# Sheet1.net
KiCad netlist of a schematic drawn in Altium Designer
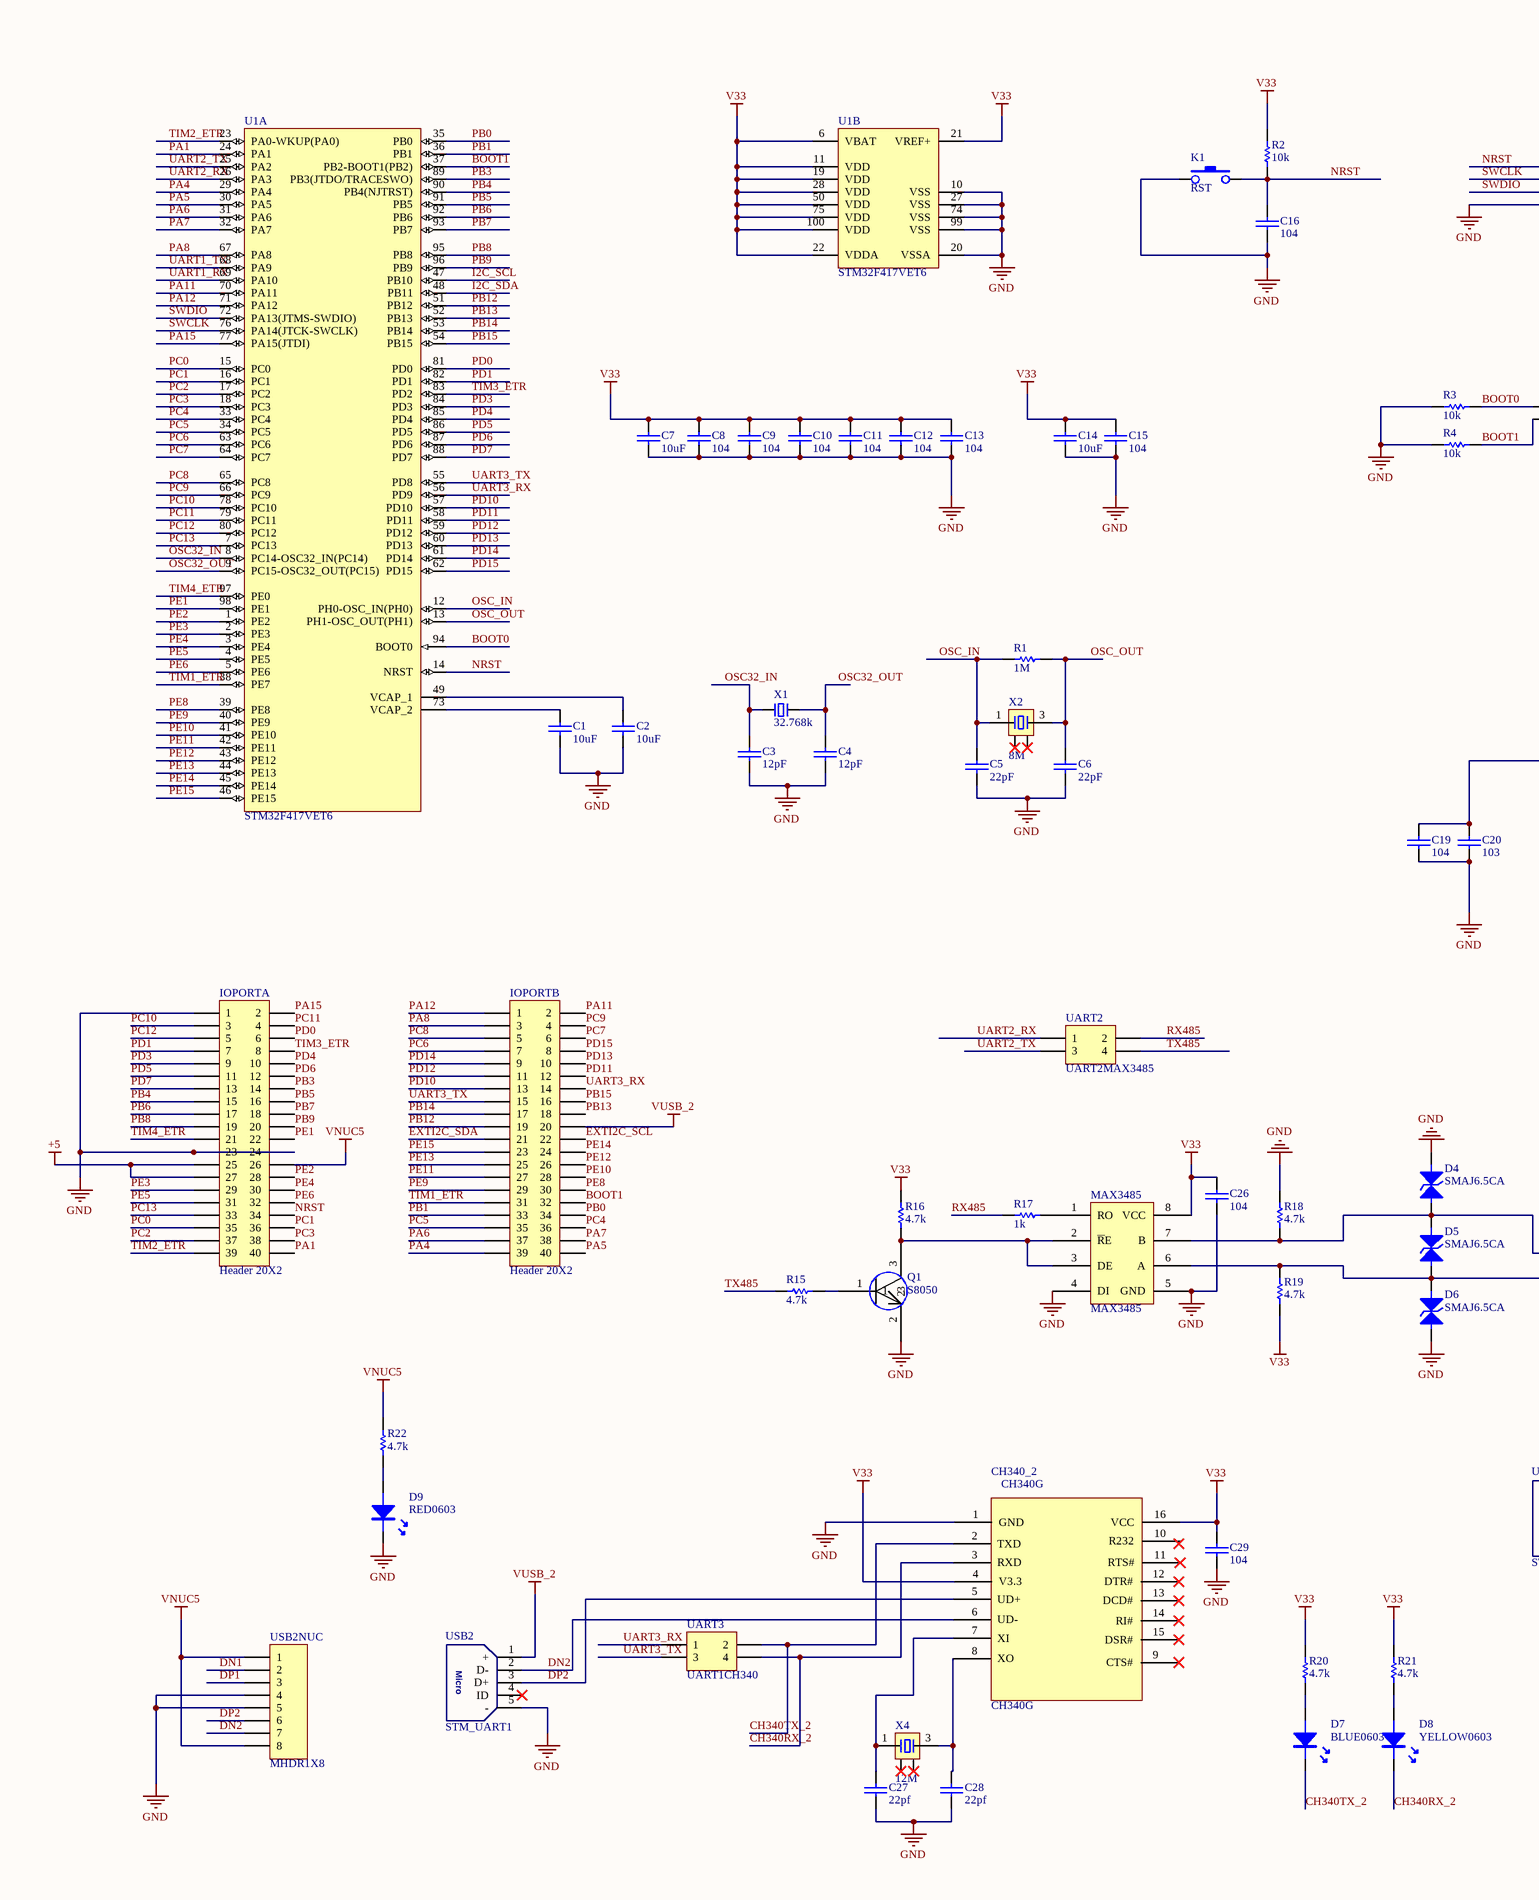
[diagram p0: Sheet1.SchDoc, left]
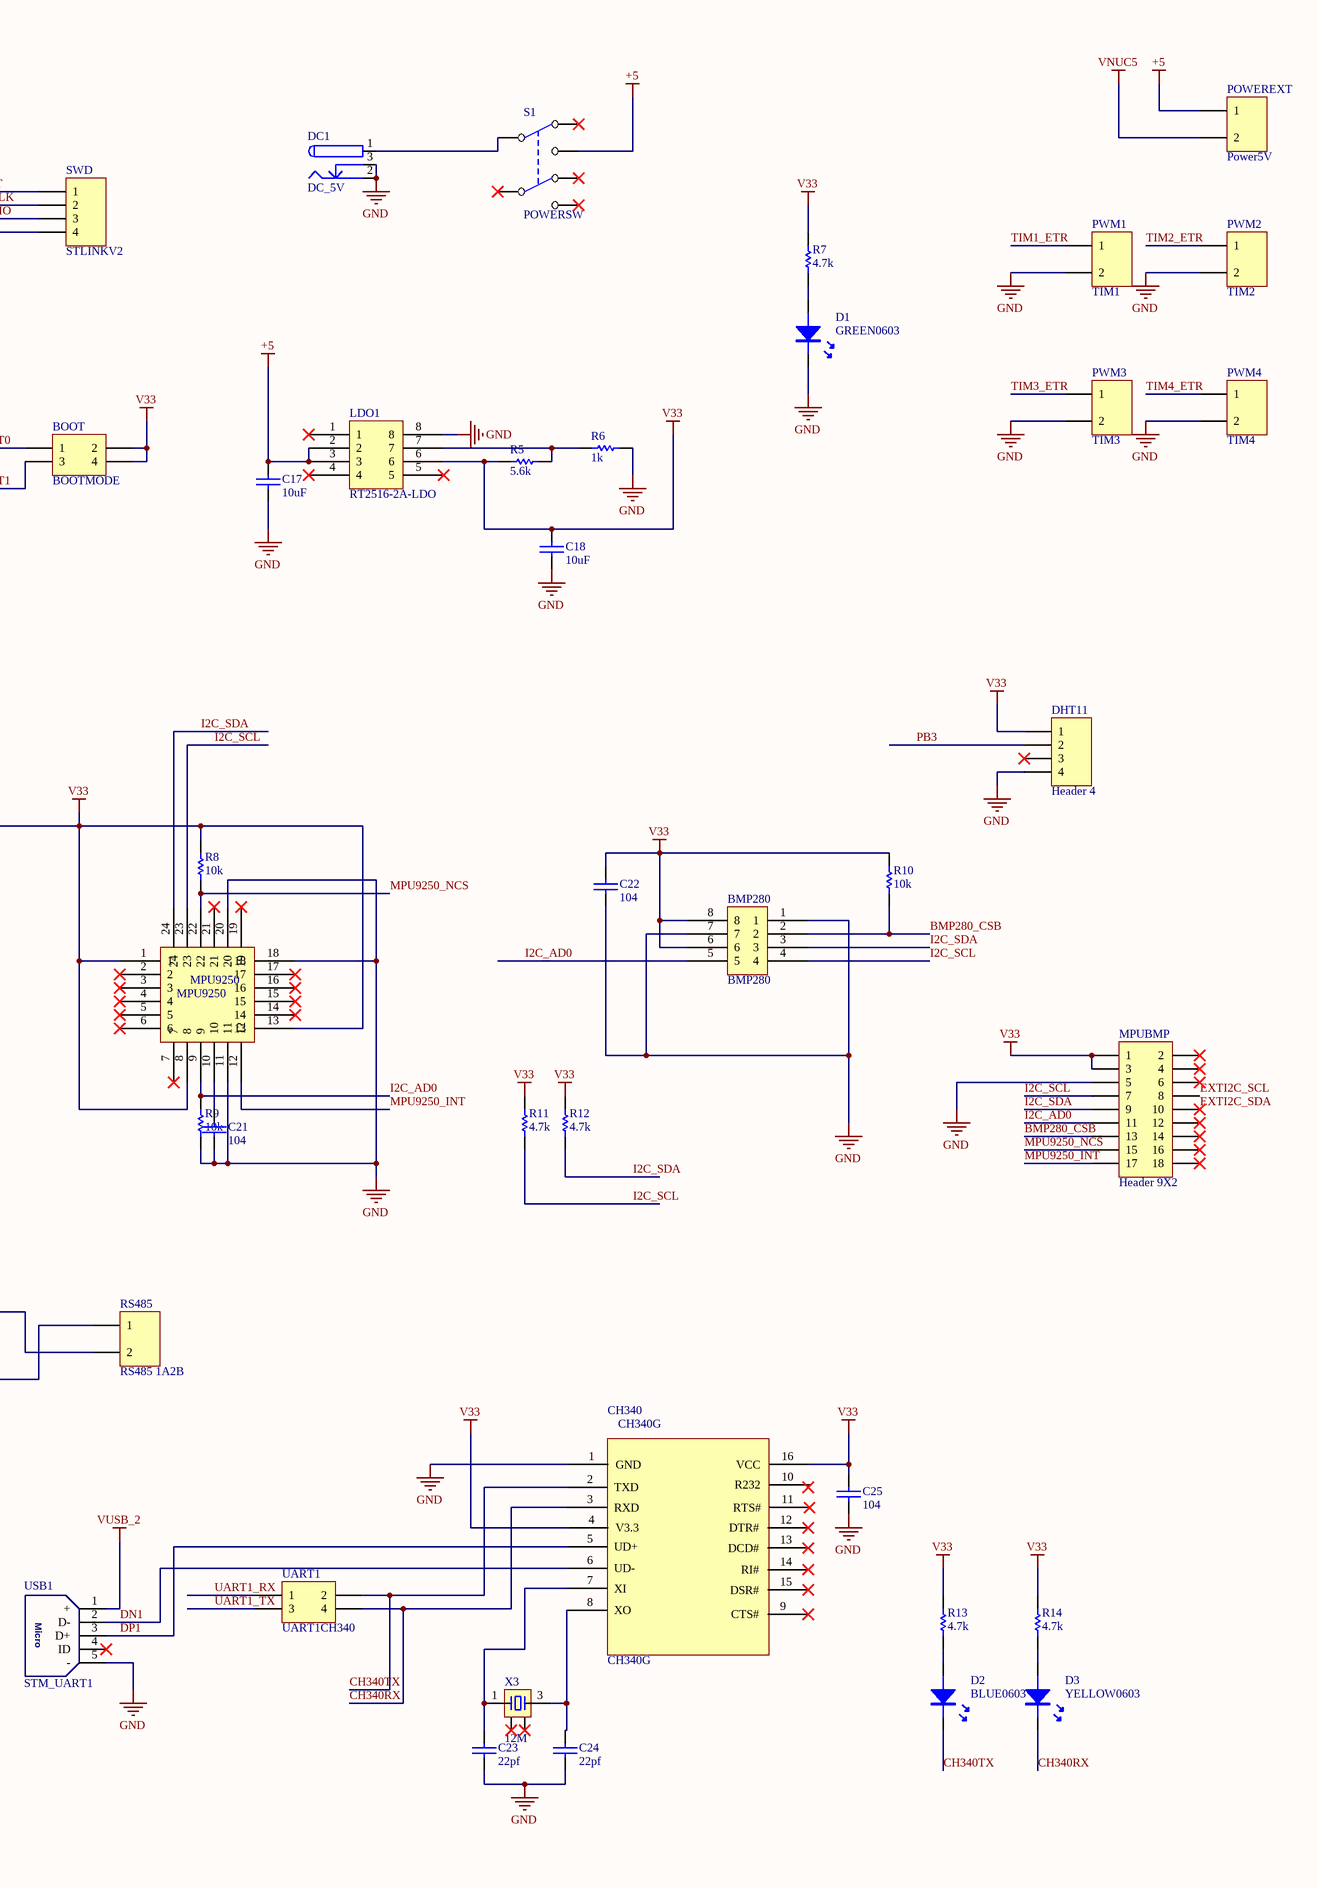
[diagram p1: Sheet1.SchDoc, right]

(export (version "E")
  (design (tool "Eeschema 10.0.6"))
  (components
    (comp (ref "BMP280")
      (value "BMP280")
      (footprint "LGA8-BOSCH")
      (libsource (lib "ics") (part "LGA8-BOSCH"))
    )
    (comp (ref "BOOT")
      (value "BOOTMODE")
      (footprint "HDR2X2")
      (description "Header, 2-Pin, Dual row")
      (fields (field (name "PUBLISHER") "Altium Limited"))
      (libsource (lib "Miscellaneous Connectors") (part "Header 2X2"))
    )
    (comp (ref "C1")
      (value "10uF")
      (footprint "0805C")
      (description "无极性电容")
      (libsource (lib "Capacitance") (part "CAP"))
    )
    (comp (ref "C2")
      (value "10uF")
      (footprint "0805C")
      (description "无极性电容")
      (libsource (lib "Capacitance") (part "CAP"))
    )
    (comp (ref "C3")
      (value "12pF")
      (footprint "0603C")
      (description "无极性电容")
      (libsource (lib "Capacitance") (part "CAP"))
    )
    (comp (ref "C4")
      (value "12pF")
      (footprint "0603C")
      (description "无极性电容")
      (libsource (lib "Capacitance") (part "CAP"))
    )
    (comp (ref "C5")
      (value "22pF")
      (footprint "0603C")
      (description "无极性电容")
      (libsource (lib "Capacitance") (part "CAP"))
    )
    (comp (ref "C6")
      (value "22pF")
      (footprint "0603C")
      (description "无极性电容")
      (libsource (lib "Capacitance") (part "CAP"))
    )
    (comp (ref "C7")
      (value "10uF")
      (footprint "0805C")
      (description "无极性电容")
      (libsource (lib "Capacitance") (part "CAP"))
    )
    (comp (ref "C8")
      (value "104")
      (footprint "0603C")
      (description "无极性电容")
      (libsource (lib "Capacitance") (part "CAP"))
    )
    (comp (ref "C9")
      (value "104")
      (footprint "0603C")
      (description "无极性电容")
      (libsource (lib "Capacitance") (part "CAP"))
    )
    (comp (ref "C10")
      (value "104")
      (footprint "0603C")
      (description "无极性电容")
      (libsource (lib "Capacitance") (part "CAP"))
    )
    (comp (ref "C11")
      (value "104")
      (footprint "0603C")
      (description "无极性电容")
      (libsource (lib "Capacitance") (part "CAP"))
    )
    (comp (ref "C12")
      (value "104")
      (footprint "0603C")
      (description "无极性电容")
      (libsource (lib "Capacitance") (part "CAP"))
    )
    (comp (ref "C13")
      (value "104")
      (footprint "0603C")
      (description "无极性电容")
      (libsource (lib "Capacitance") (part "CAP"))
    )
    (comp (ref "C14")
      (value "10uF")
      (footprint "0805C")
      (description "无极性电容")
      (libsource (lib "Capacitance") (part "CAP"))
    )
    (comp (ref "C15")
      (value "104")
      (footprint "0603C")
      (description "无极性电容")
      (libsource (lib "Capacitance") (part "CAP"))
    )
    (comp (ref "C16")
      (value "104")
      (footprint "0603C")
      (description "无极性电容")
      (libsource (lib "Capacitance") (part "CAP"))
    )
    (comp (ref "C17")
      (value "10uF")
      (footprint "0805C")
      (description "无极性电容")
      (libsource (lib "Capacitance") (part "CAP"))
    )
    (comp (ref "C18")
      (value "10uF")
      (footprint "0805C")
      (description "无极性电容")
      (libsource (lib "Capacitance") (part "CAP"))
    )
    (comp (ref "C19")
      (value "104")
      (footprint "0603C")
      (description "无极性电容")
      (libsource (lib "Capacitance") (part "CAP"))
    )
    (comp (ref "C20")
      (value "103")
      (footprint "0603C")
      (description "无极性电容")
      (libsource (lib "Capacitance") (part "CAP"))
    )
    (comp (ref "C21")
      (value "104")
      (footprint "0603C")
      (description "无极性电容")
      (libsource (lib "Capacitance") (part "CAP"))
    )
    (comp (ref "C22")
      (value "104")
      (footprint "0603C")
      (description "无极性电容")
      (libsource (lib "Capacitance") (part "CAP"))
    )
    (comp (ref "C23")
      (value "22pf")
      (footprint "0603C")
      (description "无极性电容")
      (libsource (lib "Capacitance") (part "CAP"))
    )
    (comp (ref "C24")
      (value "22pf")
      (footprint "0603C")
      (description "无极性电容")
      (libsource (lib "Capacitance") (part "CAP"))
    )
    (comp (ref "C25")
      (value "104")
      (footprint "0603C")
      (description "无极性电容")
      (libsource (lib "Capacitance") (part "CAP"))
    )
    (comp (ref "C26")
      (value "104")
      (footprint "0805C")
      (description "无极性电容")
      (libsource (lib "Capacitance") (part "CAP"))
    )
    (comp (ref "C27")
      (value "22pf")
      (footprint "0603C")
      (description "无极性电容")
      (libsource (lib "Capacitance") (part "CAP"))
    )
    (comp (ref "C28")
      (value "22pf")
      (footprint "0603C")
      (description "无极性电容")
      (libsource (lib "Capacitance") (part "CAP"))
    )
    (comp (ref "C29")
      (value "104")
      (footprint "0603C")
      (description "无极性电容")
      (libsource (lib "Capacitance") (part "CAP"))
    )
    (comp (ref "CH340")
      (value "CH340G")
      (footprint "SOIC127P600X170-16N")
      (libsource (lib "CH340G") (part "Component_1"))
    )
    (comp (ref "CH340_2")
      (value "CH340G")
      (footprint "SOIC127P600X170-16N")
      (libsource (lib "CH340G") (part "Component_1"))
    )
    (comp (ref "D1") (value "GREEN0603") (footprint "LED-0603G") (libsource (lib "LED") (part "LED")))
    (comp (ref "D2") (value "BLUE0603") (footprint "LED-0603B") (libsource (lib "LED") (part "LED")))
    (comp (ref "D3") (value "YELLOW0603") (footprint "LED-0603Y") (libsource (lib "LED") (part "LED")))
    (comp (ref "D4")
      (value "SMAJ6.5CA")
      (footprint "SMA/DO-214AC")
      (description "双向瞬态抑制二极管")
      (libsource (lib "DIODE") (part "TVS"))
    )
    (comp (ref "D5")
      (value "SMAJ6.5CA")
      (footprint "SMA/DO-214AC")
      (description "双向瞬态抑制二极管")
      (libsource (lib "DIODE") (part "TVS"))
    )
    (comp (ref "D6")
      (value "SMAJ6.5CA")
      (footprint "SMA/DO-214AC")
      (description "双向瞬态抑制二极管")
      (libsource (lib "DIODE") (part "TVS"))
    )
    (comp (ref "D7") (value "BLUE0603") (footprint "LED-0603B") (libsource (lib "LED") (part "LED")))
    (comp (ref "D8") (value "YELLOW0603") (footprint "LED-0603Y") (libsource (lib "LED") (part "LED")))
    (comp (ref "D9") (value "RED0603") (footprint "LED-0603W") (libsource (lib "LED") (part "LED")))
    (comp (ref "DC1") (value "DC_5V") (footprint "DC-050") (libsource (lib "Power") (part "DC_Socket")))
    (comp (ref "DHT11")
      (value "Header 4")
      (footprint "HDR1X4")
      (description "Header, 4-Pin")
      (fields (field (name "PUBLISHER") "Altium Limited"))
      (libsource (lib "Miscellaneous Connectors") (part "Header 4"))
    )
    (comp (ref "IOPORTA")
      (value "Header 20X2")
      (footprint "HDR2X20")
      (description "Header, 20-Pin, Dual row")
      (fields (field (name "PUBLISHER") "Altium Limited"))
      (libsource (lib "Miscellaneous Connectors") (part "Header 20X2"))
    )
    (comp (ref "IOPORTB")
      (value "Header 20X2")
      (footprint "HDR2X20")
      (description "Header, 20-Pin, Dual row")
      (fields (field (name "PUBLISHER") "Altium Limited"))
      (libsource (lib "Miscellaneous Connectors") (part "Header 20X2"))
    )
    (comp (ref "K1") (value "RST") (footprint "DIP-6X6X5") (libsource (lib "轻触开关") (part "KEY")))
    (comp (ref "LDO1") (value "RT2516-2A-LDO") (footprint "SOP8") (libsource (lib "电源IC") (part "RT2516")))
    (comp (ref "MAX3485") (value "MAX3485") (footprint "SOP8") (libsource (lib "通讯系列IC") (part "MAX481")))
    (comp (ref "MPU9250") (value "MPU9250") (footprint "QFN24-9250") (libsource (lib "ics") (part "QFN24")))
    (comp (ref "MPUBMP")
      (value "Header 9X2")
      (footprint "HDR2X9")
      (description "Header, 9-Pin, Dual row")
      (fields (field (name "PUBLISHER") "Altium Limited"))
      (libsource (lib "Miscellaneous Connectors") (part "Header 9X2"))
    )
    (comp (ref "POWEREXT")
      (value "Power5V")
      (footprint "KF301-2P")
      (libsource (lib "接线端子") (part "Connector-2P"))
    )
    (comp (ref "PWM1") (value "TIM1") (footprint "KF301-2P") (libsource (lib "接线端子") (part "Connector-2P")))
    (comp (ref "PWM2") (value "TIM2") (footprint "KF301-2P") (libsource (lib "接线端子") (part "Connector-2P")))
    (comp (ref "PWM3") (value "TIM3") (footprint "KF301-2P") (libsource (lib "接线端子") (part "Connector-2P")))
    (comp (ref "PWM4") (value "TIM4") (footprint "KF301-2P") (libsource (lib "接线端子") (part "Connector-2P")))
    (comp (ref "Q1") (value "S8050") (footprint "SOT23") (libsource (lib "ics") (part "S9014")))
    (comp (ref "R1") (value "1M") (footprint "0603R") (libsource (lib "Resistance") (part "RES")))
    (comp (ref "R2") (value "10k") (footprint "0603R") (libsource (lib "Resistance") (part "RES")))
    (comp (ref "R3") (value "10k") (footprint "0603R") (libsource (lib "Resistance") (part "RES")))
    (comp (ref "R4") (value "10k") (footprint "0603R") (libsource (lib "Resistance") (part "RES")))
    (comp (ref "R5") (value "5.6k") (footprint "0603R") (libsource (lib "Resistance") (part "RES")))
    (comp (ref "R6") (value "1k") (footprint "0603R") (libsource (lib "Resistance") (part "RES")))
    (comp (ref "R7") (value "4.7k") (footprint "0603R") (libsource (lib "Resistance") (part "RES")))
    (comp (ref "R8") (value "10k") (footprint "0603R") (libsource (lib "Resistance") (part "RES")))
    (comp (ref "R9") (value "10k") (footprint "0603R") (libsource (lib "Resistance") (part "RES")))
    (comp (ref "R10") (value "10k") (footprint "0603R") (libsource (lib "Resistance") (part "RES")))
    (comp (ref "R11") (value "4.7k") (footprint "0603R") (libsource (lib "Resistance") (part "RES")))
    (comp (ref "R12") (value "4.7k") (footprint "0603R") (libsource (lib "Resistance") (part "RES")))
    (comp (ref "R13") (value "4.7k") (footprint "0603R") (libsource (lib "Resistance") (part "RES")))
    (comp (ref "R14") (value "4.7k") (footprint "0603R") (libsource (lib "Resistance") (part "RES")))
    (comp (ref "R15") (value "4.7k") (footprint "0603R") (libsource (lib "Resistance") (part "RES")))
    (comp (ref "R16") (value "4.7k") (footprint "0603R") (libsource (lib "Resistance") (part "RES")))
    (comp (ref "R17") (value "1k") (footprint "0603R") (libsource (lib "Resistance") (part "RES")))
    (comp (ref "R18") (value "4.7k") (footprint "0603R") (libsource (lib "Resistance") (part "RES")))
    (comp (ref "R19") (value "4.7k") (footprint "0603R") (libsource (lib "Resistance") (part "RES")))
    (comp (ref "R20") (value "4.7k") (footprint "0603R") (libsource (lib "Resistance") (part "RES")))
    (comp (ref "R21") (value "4.7k") (footprint "0603R") (libsource (lib "Resistance") (part "RES")))
    (comp (ref "R22") (value "4.7k") (footprint "0603R") (libsource (lib "Resistance") (part "RES")))
    (comp (ref "RS485")
      (value "RS485 1A2B")
      (footprint "KF301-2P")
      (libsource (lib "接线端子") (part "Connector-2P"))
    )
    (comp (ref "S1")
      (value "POWERSW")
      (footprint "KFT DIP-7X7")
      (libsource (lib "电源开关") (part "KFT DIP-7X7"))
    )
    (comp (ref "SWD")
      (value "STLINKV2")
      (footprint "HDR1X4")
      (description "Header, 4-Pin")
      (fields (field (name "PUBLISHER") "Altium Limited"))
      (libsource (lib "Miscellaneous Connectors") (part "Header 4"))
    )
    (comp (ref "U1")
      (value "STM32F417VET6")
      (footprint "STM-LQFP100_N")
      (fields (field (name "MANUFACTURER") "STMicroelectronics"))
      (libsource (lib "STMicroelectronics STM32 F4") (part "STM32F417VET6"))
    )
    (comp (ref "UART1")
      (value "UART1CH340")
      (footprint "HDR2X2")
      (description "Header, 2-Pin, Dual row")
      (fields (field (name "PUBLISHER") "Altium Limited"))
      (libsource (lib "Miscellaneous Connectors") (part "Header 2X2"))
    )
    (comp (ref "UART2")
      (value "UART2MAX3485")
      (footprint "HDR2X2")
      (description "Header, 2-Pin, Dual row")
      (fields (field (name "PUBLISHER") "Altium Limited"))
      (libsource (lib "Miscellaneous Connectors") (part "Header 2X2"))
    )
    (comp (ref "UART3")
      (value "UART1CH340")
      (footprint "HDR2X2")
      (description "Header, 2-Pin, Dual row")
      (fields (field (name "PUBLISHER") "Altium Limited"))
      (libsource (lib "Miscellaneous Connectors") (part "Header 2X2"))
    )
    (comp (ref "USB1")
      (value "STM_UART1")
      (footprint "USB-micro_B")
      (libsource (lib "USB") (part "Micro-USB"))
    )
    (comp (ref "USB2")
      (value "STM_UART1")
      (footprint "USB-micro_B")
      (libsource (lib "USB") (part "Micro-USB"))
    )
    (comp (ref "USB2NUC")
      (value "MHDR1X8")
      (footprint "MHDR1X8")
      (description "Header, 8-Pin")
      (fields (field (name "PUBLISHER") "Altium Limited"))
      (libsource (lib "Miscellaneous Connectors") (part "MHDR1X8"))
    )
    (comp (ref "X1")
      (value "32.768k")
      (footprint "X3215")
      (description "2脚无源脚晶振")
      (libsource (lib "晶振") (part "XTAL-2P"))
    )
    (comp (ref "X2")
      (value "8M")
      (footprint "OSC 3225-4P")
      (description "4脚无源晶振")
      (libsource (lib "晶振") (part "XTAL-4P"))
    )
    (comp (ref "X3")
      (value "12M")
      (footprint "OSC 3225-4P")
      (description "4脚无源晶振")
      (libsource (lib "晶振") (part "XTAL-4P"))
    )
    (comp (ref "X4")
      (value "12M")
      (footprint "OSC 3225-4P")
      (description "4脚无源晶振")
      (libsource (lib "晶振") (part "XTAL-4P"))
    )
  )
  (nets
    (net (code "1") (name "+5") (class "Default")
      (node (ref "C17") (pin "2") (pinfunction "2_2") (pintype "passive"))
      (node (ref "IOPORTA") (pin "25") (pinfunction "25_25") (pintype "passive"))
      (node (ref "IOPORTA") (pin "27") (pinfunction "27_27") (pintype "passive"))
      (node (ref "LDO1") (pin "2") (pinfunction "2_2") (pintype "passive"))
      (node (ref "LDO1") (pin "3") (pinfunction "3_3") (pintype "passive"))
      (node (ref "POWEREXT") (pin "1") (pinfunction "1_1") (pintype "passive"))
      (node (ref "S1") (pin "1") (pinfunction "1_1") (pintype "passive"))
    )
    (net (code "2") (name "/BMP280_CSB") (class "Default")
      (node (ref "BMP280") (pin "2") (pinfunction "2_2") (pintype "passive"))
      (node (ref "MPUBMP") (pin "13") (pinfunction "13_13") (pintype "passive"))
      (node (ref "R10") (pin "1") (pinfunction "1_1") (pintype "passive"))
    )
    (net (code "3") (name "/BOOT0") (class "Default")
      (node (ref "BOOT") (pin "1") (pinfunction "1_1") (pintype "passive"))
      (node (ref "R3") (pin "1") (pinfunction "1_1") (pintype "passive"))
      (node (ref "U1") (pin "94") (pinfunction "BOOT0_94") (pintype "input"))
    )
    (net (code "4") (name "/BOOT1") (class "Default")
      (node (ref "BOOT") (pin "3") (pinfunction "3_3") (pintype "passive"))
      (node (ref "IOPORTB") (pin "32") (pinfunction "32_32") (pintype "passive"))
      (node (ref "R4") (pin "1") (pinfunction "1_1") (pintype "passive"))
      (node (ref "U1") (pin "37") (pinfunction "PB2-BOOT1(PB2)_37") (pintype "bidirectional"))
    )
    (net (code "5") (name "/CH340RX") (class "Default")
      (node (ref "CH340") (pin "3") (pinfunction "RXD_3") (pintype "passive"))
      (node (ref "D3") (pin "K") (pinfunction "K_K") (pintype "passive"))
      (node (ref "UART1") (pin "4") (pinfunction "4_4") (pintype "passive"))
    )
    (net (code "6") (name "/CH340RX_2") (class "Default")
      (node (ref "CH340_2") (pin "3") (pinfunction "RXD_3") (pintype "passive"))
      (node (ref "D8") (pin "K") (pinfunction "K_K") (pintype "passive"))
      (node (ref "UART3") (pin "4") (pinfunction "4_4") (pintype "passive"))
    )
    (net (code "7") (name "/CH340TX") (class "Default")
      (node (ref "CH340") (pin "2") (pinfunction "TXD_2") (pintype "passive"))
      (node (ref "D2") (pin "K") (pinfunction "K_K") (pintype "passive"))
      (node (ref "UART1") (pin "2") (pinfunction "2_2") (pintype "passive"))
    )
    (net (code "8") (name "/CH340TX_2") (class "Default")
      (node (ref "CH340_2") (pin "2") (pinfunction "TXD_2") (pintype "passive"))
      (node (ref "D7") (pin "K") (pinfunction "K_K") (pintype "passive"))
      (node (ref "UART3") (pin "2") (pinfunction "2_2") (pintype "passive"))
    )
    (net (code "9") (name "/DN1") (class "Default")
      (node (ref "CH340") (pin "6") (pinfunction "UD-_6") (pintype "passive"))
      (node (ref "USB1") (pin "2") (pinfunction "D-_2") (pintype "passive"))
      (node (ref "USB2NUC") (pin "2") (pinfunction "2_2") (pintype "passive"))
    )
    (net (code "10") (name "/DN2") (class "Default")
      (node (ref "CH340_2") (pin "6") (pinfunction "UD-_6") (pintype "passive"))
      (node (ref "USB2") (pin "2") (pinfunction "D-_2") (pintype "passive"))
      (node (ref "USB2NUC") (pin "7") (pinfunction "7_7") (pintype "passive"))
    )
    (net (code "11") (name "/DP1") (class "Default")
      (node (ref "CH340") (pin "5") (pinfunction "UD+_5") (pintype "passive"))
      (node (ref "USB1") (pin "3") (pinfunction "D+_3") (pintype "passive"))
      (node (ref "USB2NUC") (pin "3") (pinfunction "3_3") (pintype "passive"))
    )
    (net (code "12") (name "/DP2") (class "Default")
      (node (ref "CH340_2") (pin "5") (pinfunction "UD+_5") (pintype "passive"))
      (node (ref "USB2") (pin "3") (pinfunction "D+_3") (pintype "passive"))
      (node (ref "USB2NUC") (pin "6") (pinfunction "6_6") (pintype "passive"))
    )
    (net (code "13") (name "/EXTI2C_SCL") (class "Default")
      (node (ref "IOPORTB") (pin "22") (pinfunction "22_22") (pintype "passive"))
      (node (ref "MPUBMP") (pin "8") (pinfunction "8_8") (pintype "passive"))
    )
    (net (code "14") (name "/EXTI2C_SDA") (class "Default")
      (node (ref "IOPORTB") (pin "21") (pinfunction "21_21") (pintype "passive"))
      (node (ref "MPUBMP") (pin "10") (pinfunction "10_10") (pintype "passive"))
    )
    (net (code "15") (name "/I2C_AD0") (class "Default")
      (node (ref "BMP280") (pin "5") (pinfunction "5_5") (pintype "passive"))
      (node (ref "MPU9250") (pin "9") (pinfunction "9_9") (pintype "passive"))
      (node (ref "MPUBMP") (pin "11") (pinfunction "11_11") (pintype "passive"))
      (node (ref "R9") (pin "2") (pinfunction "2_2") (pintype "passive"))
    )
    (net (code "16") (name "/I2C_SCL") (class "Default")
      (node (ref "BMP280") (pin "4") (pinfunction "4_4") (pintype "passive"))
      (node (ref "MPU9250") (pin "23") (pinfunction "23_23") (pintype "passive"))
      (node (ref "MPUBMP") (pin "7") (pinfunction "7_7") (pintype "passive"))
      (node (ref "R11") (pin "1") (pinfunction "1_1") (pintype "passive"))
      (node (ref "U1") (pin "47") (pinfunction "PB10_47") (pintype "bidirectional"))
    )
    (net (code "17") (name "/I2C_SDA") (class "Default")
      (node (ref "BMP280") (pin "3") (pinfunction "3_3") (pintype "passive"))
      (node (ref "MPU9250") (pin "24") (pinfunction "24_24") (pintype "passive"))
      (node (ref "MPUBMP") (pin "9") (pinfunction "9_9") (pintype "passive"))
      (node (ref "R12") (pin "1") (pinfunction "1_1") (pintype "passive"))
      (node (ref "U1") (pin "48") (pinfunction "PB11_48") (pintype "bidirectional"))
    )
    (net (code "18") (name "/MPU9250_INT") (class "Default")
      (node (ref "MPU9250") (pin "12") (pinfunction "12_12") (pintype "passive"))
      (node (ref "MPUBMP") (pin "17") (pinfunction "17_17") (pintype "passive"))
    )
    (net (code "19") (name "/MPU9250_NCS") (class "Default")
      (node (ref "MPU9250") (pin "22") (pinfunction "22_22") (pintype "passive"))
      (node (ref "MPUBMP") (pin "15") (pinfunction "15_15") (pintype "passive"))
      (node (ref "R8") (pin "1") (pinfunction "1_1") (pintype "passive"))
    )
    (net (code "20") (name "/NRST") (class "Default")
      (node (ref "C16") (pin "2") (pinfunction "2_2") (pintype "passive"))
      (node (ref "IOPORTA") (pin "34") (pinfunction "34_34") (pintype "passive"))
      (node (ref "K1") (pin "3") (pinfunction "3_3") (pintype "passive"))
      (node (ref "R2") (pin "1") (pinfunction "1_1") (pintype "passive"))
      (node (ref "SWD") (pin "1") (pinfunction "1_1") (pintype "passive"))
      (node (ref "U1") (pin "14") (pinfunction "NRST_14") (pintype "bidirectional"))
    )
    (net (code "21") (name "/OSC32_IN") (class "Default")
      (node (ref "C3") (pin "2") (pinfunction "2_2") (pintype "passive"))
      (node (ref "U1") (pin "8") (pinfunction "PC14-OSC32_IN(PC14)_8") (pintype "bidirectional"))
      (node (ref "X1") (pin "2") (pinfunction "2_2") (pintype "passive"))
    )
    (net (code "22") (name "/OSC32_OUT") (class "Default")
      (node (ref "C4") (pin "2") (pinfunction "2_2") (pintype "passive"))
      (node (ref "U1") (pin "9") (pinfunction "PC15-OSC32_OUT(PC15)_9") (pintype "bidirectional"))
      (node (ref "X1") (pin "1") (pinfunction "1_1") (pintype "passive"))
    )
    (net (code "23") (name "/OSC_IN") (class "Default")
      (node (ref "C5") (pin "2") (pinfunction "2_2") (pintype "passive"))
      (node (ref "R1") (pin "1") (pinfunction "1_1") (pintype "passive"))
      (node (ref "U1") (pin "12") (pinfunction "PH0-OSC_IN(PH0)_12") (pintype "bidirectional"))
      (node (ref "X2") (pin "1") (pinfunction "1_1") (pintype "passive"))
    )
    (net (code "24") (name "/OSC_OUT") (class "Default")
      (node (ref "C6") (pin "2") (pinfunction "2_2") (pintype "passive"))
      (node (ref "R1") (pin "2") (pinfunction "2_2") (pintype "passive"))
      (node (ref "U1") (pin "13") (pinfunction "PH1-OSC_OUT(PH1)_13") (pintype "bidirectional"))
      (node (ref "X2") (pin "3") (pinfunction "3_3") (pintype "passive"))
    )
    (net (code "25") (name "/PA1") (class "Default")
      (node (ref "IOPORTA") (pin "40") (pinfunction "40_40") (pintype "passive"))
      (node (ref "U1") (pin "24") (pinfunction "PA1_24") (pintype "bidirectional"))
    )
    (net (code "26") (name "/PA4") (class "Default")
      (node (ref "IOPORTB") (pin "39") (pinfunction "39_39") (pintype "passive"))
      (node (ref "U1") (pin "29") (pinfunction "PA4_29") (pintype "bidirectional"))
    )
    (net (code "27") (name "/PA5") (class "Default")
      (node (ref "IOPORTB") (pin "40") (pinfunction "40_40") (pintype "passive"))
      (node (ref "U1") (pin "30") (pinfunction "PA5_30") (pintype "bidirectional"))
    )
    (net (code "28") (name "/PA6") (class "Default")
      (node (ref "IOPORTB") (pin "37") (pinfunction "37_37") (pintype "passive"))
      (node (ref "U1") (pin "31") (pinfunction "PA6_31") (pintype "bidirectional"))
    )
    (net (code "29") (name "/PA7") (class "Default")
      (node (ref "IOPORTB") (pin "38") (pinfunction "38_38") (pintype "passive"))
      (node (ref "U1") (pin "32") (pinfunction "PA7_32") (pintype "bidirectional"))
    )
    (net (code "30") (name "/PA8") (class "Default")
      (node (ref "IOPORTB") (pin "3") (pinfunction "3_3") (pintype "passive"))
      (node (ref "U1") (pin "67") (pinfunction "PA8_67") (pintype "bidirectional"))
    )
    (net (code "31") (name "/PA11") (class "Default")
      (node (ref "IOPORTB") (pin "2") (pinfunction "2_2") (pintype "passive"))
      (node (ref "U1") (pin "70") (pinfunction "PA11_70") (pintype "bidirectional"))
    )
    (net (code "32") (name "/PA12") (class "Default")
      (node (ref "IOPORTB") (pin "1") (pinfunction "1_1") (pintype "passive"))
      (node (ref "U1") (pin "71") (pinfunction "PA12_71") (pintype "bidirectional"))
    )
    (net (code "33") (name "/PA15") (class "Default")
      (node (ref "IOPORTA") (pin "2") (pinfunction "2_2") (pintype "passive"))
      (node (ref "U1") (pin "77") (pinfunction "PA15(JTDI)_77") (pintype "bidirectional"))
    )
    (net (code "34") (name "/PB0") (class "Default")
      (node (ref "IOPORTB") (pin "34") (pinfunction "34_34") (pintype "passive"))
      (node (ref "U1") (pin "35") (pinfunction "PB0_35") (pintype "bidirectional"))
    )
    (net (code "35") (name "/PB1") (class "Default")
      (node (ref "IOPORTB") (pin "33") (pinfunction "33_33") (pintype "passive"))
      (node (ref "U1") (pin "36") (pinfunction "PB1_36") (pintype "bidirectional"))
    )
    (net (code "36") (name "/PB3") (class "Default")
      (node (ref "DHT11") (pin "2") (pinfunction "2_2") (pintype "passive"))
      (node (ref "IOPORTA") (pin "14") (pinfunction "14_14") (pintype "passive"))
      (node (ref "U1") (pin "89") (pinfunction "PB3(JTDO/TRACESWO)_89") (pintype "bidirectional"))
    )
    (net (code "37") (name "/PB4") (class "Default")
      (node (ref "IOPORTA") (pin "15") (pinfunction "15_15") (pintype "passive"))
      (node (ref "U1") (pin "90") (pinfunction "PB4(NJTRST)_90") (pintype "bidirectional"))
    )
    (net (code "38") (name "/PB5") (class "Default")
      (node (ref "IOPORTA") (pin "16") (pinfunction "16_16") (pintype "passive"))
      (node (ref "U1") (pin "91") (pinfunction "PB5_91") (pintype "bidirectional"))
    )
    (net (code "39") (name "/PB6") (class "Default")
      (node (ref "IOPORTA") (pin "17") (pinfunction "17_17") (pintype "passive"))
      (node (ref "U1") (pin "92") (pinfunction "PB6_92") (pintype "bidirectional"))
    )
    (net (code "40") (name "/PB7") (class "Default")
      (node (ref "IOPORTA") (pin "18") (pinfunction "18_18") (pintype "passive"))
      (node (ref "U1") (pin "93") (pinfunction "PB7_93") (pintype "bidirectional"))
    )
    (net (code "41") (name "/PB8") (class "Default")
      (node (ref "IOPORTA") (pin "19") (pinfunction "19_19") (pintype "passive"))
      (node (ref "U1") (pin "95") (pinfunction "PB8_95") (pintype "bidirectional"))
    )
    (net (code "42") (name "/PB9") (class "Default")
      (node (ref "IOPORTA") (pin "20") (pinfunction "20_20") (pintype "passive"))
      (node (ref "U1") (pin "96") (pinfunction "PB9_96") (pintype "bidirectional"))
    )
    (net (code "43") (name "/PB12") (class "Default")
      (node (ref "IOPORTB") (pin "19") (pinfunction "19_19") (pintype "passive"))
      (node (ref "U1") (pin "51") (pinfunction "PB12_51") (pintype "bidirectional"))
    )
    (net (code "44") (name "/PB13") (class "Default")
      (node (ref "IOPORTB") (pin "18") (pinfunction "18_18") (pintype "passive"))
      (node (ref "U1") (pin "52") (pinfunction "PB13_52") (pintype "bidirectional"))
    )
    (net (code "45") (name "/PB14") (class "Default")
      (node (ref "IOPORTB") (pin "17") (pinfunction "17_17") (pintype "passive"))
      (node (ref "U1") (pin "53") (pinfunction "PB14_53") (pintype "bidirectional"))
    )
    (net (code "46") (name "/PB15") (class "Default")
      (node (ref "IOPORTB") (pin "16") (pinfunction "16_16") (pintype "passive"))
      (node (ref "U1") (pin "54") (pinfunction "PB15_54") (pintype "bidirectional"))
    )
    (net (code "47") (name "/PC0") (class "Default")
      (node (ref "IOPORTA") (pin "35") (pinfunction "35_35") (pintype "passive"))
      (node (ref "U1") (pin "15") (pinfunction "PC0_15") (pintype "bidirectional"))
    )
    (net (code "48") (name "/PC1") (class "Default")
      (node (ref "IOPORTA") (pin "36") (pinfunction "36_36") (pintype "passive"))
      (node (ref "U1") (pin "16") (pinfunction "PC1_16") (pintype "bidirectional"))
    )
    (net (code "49") (name "/PC2") (class "Default")
      (node (ref "IOPORTA") (pin "37") (pinfunction "37_37") (pintype "passive"))
      (node (ref "U1") (pin "17") (pinfunction "PC2_17") (pintype "bidirectional"))
    )
    (net (code "50") (name "/PC3") (class "Default")
      (node (ref "IOPORTA") (pin "38") (pinfunction "38_38") (pintype "passive"))
      (node (ref "U1") (pin "18") (pinfunction "PC3_18") (pintype "bidirectional"))
    )
    (net (code "51") (name "/PC4") (class "Default")
      (node (ref "IOPORTB") (pin "36") (pinfunction "36_36") (pintype "passive"))
      (node (ref "U1") (pin "33") (pinfunction "PC4_33") (pintype "bidirectional"))
    )
    (net (code "52") (name "/PC5") (class "Default")
      (node (ref "IOPORTB") (pin "35") (pinfunction "35_35") (pintype "passive"))
      (node (ref "U1") (pin "34") (pinfunction "PC5_34") (pintype "bidirectional"))
    )
    (net (code "53") (name "/PC6") (class "Default")
      (node (ref "IOPORTB") (pin "7") (pinfunction "7_7") (pintype "passive"))
      (node (ref "U1") (pin "63") (pinfunction "PC6_63") (pintype "bidirectional"))
    )
    (net (code "54") (name "/PC7") (class "Default")
      (node (ref "IOPORTB") (pin "6") (pinfunction "6_6") (pintype "passive"))
      (node (ref "U1") (pin "64") (pinfunction "PC7_64") (pintype "bidirectional"))
    )
    (net (code "55") (name "/PC8") (class "Default")
      (node (ref "IOPORTB") (pin "5") (pinfunction "5_5") (pintype "passive"))
      (node (ref "U1") (pin "65") (pinfunction "PC8_65") (pintype "bidirectional"))
    )
    (net (code "56") (name "/PC9") (class "Default")
      (node (ref "IOPORTB") (pin "4") (pinfunction "4_4") (pintype "passive"))
      (node (ref "U1") (pin "66") (pinfunction "PC9_66") (pintype "bidirectional"))
    )
    (net (code "57") (name "/PC10") (class "Default")
      (node (ref "IOPORTA") (pin "3") (pinfunction "3_3") (pintype "passive"))
      (node (ref "U1") (pin "78") (pinfunction "PC10_78") (pintype "bidirectional"))
    )
    (net (code "58") (name "/PC11") (class "Default")
      (node (ref "IOPORTA") (pin "4") (pinfunction "4_4") (pintype "passive"))
      (node (ref "U1") (pin "79") (pinfunction "PC11_79") (pintype "bidirectional"))
    )
    (net (code "59") (name "/PC12") (class "Default")
      (node (ref "IOPORTA") (pin "5") (pinfunction "5_5") (pintype "passive"))
      (node (ref "U1") (pin "80") (pinfunction "PC12_80") (pintype "bidirectional"))
    )
    (net (code "60") (name "/PC13") (class "Default")
      (node (ref "IOPORTA") (pin "33") (pinfunction "33_33") (pintype "passive"))
      (node (ref "U1") (pin "7") (pinfunction "PC13_7") (pintype "bidirectional"))
    )
    (net (code "61") (name "/PD0") (class "Default")
      (node (ref "IOPORTA") (pin "6") (pinfunction "6_6") (pintype "passive"))
      (node (ref "U1") (pin "81") (pinfunction "PD0_81") (pintype "bidirectional"))
    )
    (net (code "62") (name "/PD1") (class "Default")
      (node (ref "IOPORTA") (pin "7") (pinfunction "7_7") (pintype "passive"))
      (node (ref "U1") (pin "82") (pinfunction "PD1_82") (pintype "bidirectional"))
    )
    (net (code "63") (name "/PD3") (class "Default")
      (node (ref "IOPORTA") (pin "9") (pinfunction "9_9") (pintype "passive"))
      (node (ref "U1") (pin "84") (pinfunction "PD3_84") (pintype "bidirectional"))
    )
    (net (code "64") (name "/PD4") (class "Default")
      (node (ref "IOPORTA") (pin "10") (pinfunction "10_10") (pintype "passive"))
      (node (ref "U1") (pin "85") (pinfunction "PD4_85") (pintype "bidirectional"))
    )
    (net (code "65") (name "/PD5") (class "Default")
      (node (ref "IOPORTA") (pin "11") (pinfunction "11_11") (pintype "passive"))
      (node (ref "U1") (pin "86") (pinfunction "PD5_86") (pintype "bidirectional"))
    )
    (net (code "66") (name "/PD6") (class "Default")
      (node (ref "IOPORTA") (pin "12") (pinfunction "12_12") (pintype "passive"))
      (node (ref "U1") (pin "87") (pinfunction "PD6_87") (pintype "bidirectional"))
    )
    (net (code "67") (name "/PD7") (class "Default")
      (node (ref "IOPORTA") (pin "13") (pinfunction "13_13") (pintype "passive"))
      (node (ref "U1") (pin "88") (pinfunction "PD7_88") (pintype "bidirectional"))
    )
    (net (code "68") (name "/PD10") (class "Default")
      (node (ref "IOPORTB") (pin "13") (pinfunction "13_13") (pintype "passive"))
      (node (ref "U1") (pin "57") (pinfunction "PD10_57") (pintype "bidirectional"))
    )
    (net (code "69") (name "/PD11") (class "Default")
      (node (ref "IOPORTB") (pin "12") (pinfunction "12_12") (pintype "passive"))
      (node (ref "U1") (pin "58") (pinfunction "PD11_58") (pintype "bidirectional"))
    )
    (net (code "70") (name "/PD12") (class "Default")
      (node (ref "IOPORTB") (pin "11") (pinfunction "11_11") (pintype "passive"))
      (node (ref "U1") (pin "59") (pinfunction "PD12_59") (pintype "bidirectional"))
    )
    (net (code "71") (name "/PD13") (class "Default")
      (node (ref "IOPORTB") (pin "10") (pinfunction "10_10") (pintype "passive"))
      (node (ref "U1") (pin "60") (pinfunction "PD13_60") (pintype "bidirectional"))
    )
    (net (code "72") (name "/PD14") (class "Default")
      (node (ref "IOPORTB") (pin "9") (pinfunction "9_9") (pintype "passive"))
      (node (ref "U1") (pin "61") (pinfunction "PD14_61") (pintype "bidirectional"))
    )
    (net (code "73") (name "/PD15") (class "Default")
      (node (ref "IOPORTB") (pin "8") (pinfunction "8_8") (pintype "passive"))
      (node (ref "U1") (pin "62") (pinfunction "PD15_62") (pintype "bidirectional"))
    )
    (net (code "74") (name "/PE1") (class "Default")
      (node (ref "IOPORTA") (pin "22") (pinfunction "22_22") (pintype "passive"))
      (node (ref "U1") (pin "98") (pinfunction "PE1_98") (pintype "bidirectional"))
    )
    (net (code "75") (name "/PE2") (class "Default")
      (node (ref "IOPORTA") (pin "28") (pinfunction "28_28") (pintype "passive"))
      (node (ref "U1") (pin "1") (pinfunction "PE2_1") (pintype "bidirectional"))
    )
    (net (code "76") (name "/PE3") (class "Default")
      (node (ref "IOPORTA") (pin "29") (pinfunction "29_29") (pintype "passive"))
      (node (ref "U1") (pin "2") (pinfunction "PE3_2") (pintype "bidirectional"))
    )
    (net (code "77") (name "/PE4") (class "Default")
      (node (ref "IOPORTA") (pin "30") (pinfunction "30_30") (pintype "passive"))
      (node (ref "U1") (pin "3") (pinfunction "PE4_3") (pintype "bidirectional"))
    )
    (net (code "78") (name "/PE5") (class "Default")
      (node (ref "IOPORTA") (pin "31") (pinfunction "31_31") (pintype "passive"))
      (node (ref "U1") (pin "4") (pinfunction "PE5_4") (pintype "bidirectional"))
    )
    (net (code "79") (name "/PE6") (class "Default")
      (node (ref "IOPORTA") (pin "32") (pinfunction "32_32") (pintype "passive"))
      (node (ref "U1") (pin "5") (pinfunction "PE6_5") (pintype "bidirectional"))
    )
    (net (code "80") (name "/PE8") (class "Default")
      (node (ref "IOPORTB") (pin "30") (pinfunction "30_30") (pintype "passive"))
      (node (ref "U1") (pin "39") (pinfunction "PE8_39") (pintype "bidirectional"))
    )
    (net (code "81") (name "/PE9") (class "Default")
      (node (ref "IOPORTB") (pin "29") (pinfunction "29_29") (pintype "passive"))
      (node (ref "U1") (pin "40") (pinfunction "PE9_40") (pintype "bidirectional"))
    )
    (net (code "82") (name "/PE10") (class "Default")
      (node (ref "IOPORTB") (pin "28") (pinfunction "28_28") (pintype "passive"))
      (node (ref "U1") (pin "41") (pinfunction "PE10_41") (pintype "bidirectional"))
    )
    (net (code "83") (name "/PE11") (class "Default")
      (node (ref "IOPORTB") (pin "27") (pinfunction "27_27") (pintype "passive"))
      (node (ref "U1") (pin "42") (pinfunction "PE11_42") (pintype "bidirectional"))
    )
    (net (code "84") (name "/PE12") (class "Default")
      (node (ref "IOPORTB") (pin "26") (pinfunction "26_26") (pintype "passive"))
      (node (ref "U1") (pin "43") (pinfunction "PE12_43") (pintype "bidirectional"))
    )
    (net (code "85") (name "/PE13") (class "Default")
      (node (ref "IOPORTB") (pin "25") (pinfunction "25_25") (pintype "passive"))
      (node (ref "U1") (pin "44") (pinfunction "PE13_44") (pintype "bidirectional"))
    )
    (net (code "86") (name "/PE14") (class "Default")
      (node (ref "IOPORTB") (pin "24") (pinfunction "24_24") (pintype "passive"))
      (node (ref "U1") (pin "45") (pinfunction "PE14_45") (pintype "bidirectional"))
    )
    (net (code "87") (name "/PE15") (class "Default")
      (node (ref "IOPORTB") (pin "23") (pinfunction "23_23") (pintype "passive"))
      (node (ref "U1") (pin "46") (pinfunction "PE15_46") (pintype "bidirectional"))
    )
    (net (code "88") (name "/RX485") (class "Default")
      (node (ref "R17") (pin "1") (pinfunction "1_1") (pintype "passive"))
      (node (ref "UART2") (pin "2") (pinfunction "2_2") (pintype "passive"))
    )
    (net (code "89") (name "/SWCLK") (class "Default")
      (node (ref "SWD") (pin "2") (pinfunction "2_2") (pintype "passive"))
      (node (ref "U1") (pin "76") (pinfunction "PA14(JTCK-SWCLK)_76") (pintype "bidirectional"))
    )
    (net (code "90") (name "/SWDIO") (class "Default")
      (node (ref "SWD") (pin "3") (pinfunction "3_3") (pintype "passive"))
      (node (ref "U1") (pin "72") (pinfunction "PA13(JTMS-SWDIO)_72") (pintype "bidirectional"))
    )
    (net (code "91") (name "/TIM1_ETR") (class "Default")
      (node (ref "IOPORTB") (pin "31") (pinfunction "31_31") (pintype "passive"))
      (node (ref "PWM1") (pin "1") (pinfunction "1_1") (pintype "passive"))
      (node (ref "U1") (pin "38") (pinfunction "PE7_38") (pintype "bidirectional"))
    )
    (net (code "92") (name "/TIM2_ETR") (class "Default")
      (node (ref "IOPORTA") (pin "39") (pinfunction "39_39") (pintype "passive"))
      (node (ref "PWM2") (pin "1") (pinfunction "1_1") (pintype "passive"))
      (node (ref "U1") (pin "23") (pinfunction "PA0-WKUP(PA0)_23") (pintype "bidirectional"))
    )
    (net (code "93") (name "/TIM3_ETR") (class "Default")
      (node (ref "IOPORTA") (pin "8") (pinfunction "8_8") (pintype "passive"))
      (node (ref "PWM3") (pin "1") (pinfunction "1_1") (pintype "passive"))
      (node (ref "U1") (pin "83") (pinfunction "PD2_83") (pintype "bidirectional"))
    )
    (net (code "94") (name "/TIM4_ETR") (class "Default")
      (node (ref "IOPORTA") (pin "21") (pinfunction "21_21") (pintype "passive"))
      (node (ref "PWM4") (pin "1") (pinfunction "1_1") (pintype "passive"))
      (node (ref "U1") (pin "97") (pinfunction "PE0_97") (pintype "bidirectional"))
    )
    (net (code "95") (name "/TX485") (class "Default")
      (node (ref "R15") (pin "1") (pinfunction "1_1") (pintype "passive"))
      (node (ref "UART2") (pin "4") (pinfunction "4_4") (pintype "passive"))
    )
    (net (code "96") (name "/UART1_RX") (class "Default")
      (node (ref "U1") (pin "69") (pinfunction "PA10_69") (pintype "bidirectional"))
      (node (ref "UART1") (pin "1") (pinfunction "1_1") (pintype "passive"))
    )
    (net (code "97") (name "/UART1_TX") (class "Default")
      (node (ref "U1") (pin "68") (pinfunction "PA9_68") (pintype "bidirectional"))
      (node (ref "UART1") (pin "3") (pinfunction "3_3") (pintype "passive"))
    )
    (net (code "98") (name "/UART2_RX") (class "Default")
      (node (ref "U1") (pin "26") (pinfunction "PA3_26") (pintype "bidirectional"))
      (node (ref "UART2") (pin "1") (pinfunction "1_1") (pintype "passive"))
    )
    (net (code "99") (name "/UART2_TX") (class "Default")
      (node (ref "U1") (pin "25") (pinfunction "PA2_25") (pintype "bidirectional"))
      (node (ref "UART2") (pin "3") (pinfunction "3_3") (pintype "passive"))
    )
    (net (code "100") (name "/UART3_RX") (class "Default")
      (node (ref "IOPORTB") (pin "14") (pinfunction "14_14") (pintype "passive"))
      (node (ref "U1") (pin "56") (pinfunction "PD9_56") (pintype "bidirectional"))
      (node (ref "UART3") (pin "1") (pinfunction "1_1") (pintype "passive"))
    )
    (net (code "101") (name "/UART3_TX") (class "Default")
      (node (ref "IOPORTB") (pin "15") (pinfunction "15_15") (pintype "passive"))
      (node (ref "U1") (pin "55") (pinfunction "PD8_55") (pintype "bidirectional"))
      (node (ref "UART3") (pin "3") (pinfunction "3_3") (pintype "passive"))
    )
    (net (code "102") (name "GND") (class "Default")
      (node (ref "BMP280") (pin "1") (pinfunction "1_1") (pintype "passive"))
      (node (ref "BMP280") (pin "7") (pinfunction "7_7") (pintype "passive"))
      (node (ref "C1") (pin "1") (pinfunction "1_1") (pintype "passive"))
      (node (ref "C10") (pin "1") (pinfunction "1_1") (pintype "passive"))
      (node (ref "C11") (pin "1") (pinfunction "1_1") (pintype "passive"))
      (node (ref "C12") (pin "1") (pinfunction "1_1") (pintype "passive"))
      (node (ref "C13") (pin "1") (pinfunction "1_1") (pintype "passive"))
      (node (ref "C14") (pin "1") (pinfunction "1_1") (pintype "passive"))
      (node (ref "C15") (pin "1") (pinfunction "1_1") (pintype "passive"))
      (node (ref "C16") (pin "1") (pinfunction "1_1") (pintype "passive"))
      (node (ref "C17") (pin "1") (pinfunction "1_1") (pintype "passive"))
      (node (ref "C18") (pin "1") (pinfunction "1_1") (pintype "passive"))
      (node (ref "C19") (pin "1") (pinfunction "1_1") (pintype "passive"))
      (node (ref "C2") (pin "1") (pinfunction "1_1") (pintype "passive"))
      (node (ref "C20") (pin "1") (pinfunction "1_1") (pintype "passive"))
      (node (ref "C21") (pin "1") (pinfunction "1_1") (pintype "passive"))
      (node (ref "C22") (pin "1") (pinfunction "1_1") (pintype "passive"))
      (node (ref "C23") (pin "1") (pinfunction "1_1") (pintype "passive"))
      (node (ref "C24") (pin "1") (pinfunction "1_1") (pintype "passive"))
      (node (ref "C25") (pin "1") (pinfunction "1_1") (pintype "passive"))
      (node (ref "C26") (pin "1") (pinfunction "1_1") (pintype "passive"))
      (node (ref "C27") (pin "1") (pinfunction "1_1") (pintype "passive"))
      (node (ref "C28") (pin "1") (pinfunction "1_1") (pintype "passive"))
      (node (ref "C29") (pin "1") (pinfunction "1_1") (pintype "passive"))
      (node (ref "C3") (pin "1") (pinfunction "1_1") (pintype "passive"))
      (node (ref "C4") (pin "1") (pinfunction "1_1") (pintype "passive"))
      (node (ref "C5") (pin "1") (pinfunction "1_1") (pintype "passive"))
      (node (ref "C6") (pin "1") (pinfunction "1_1") (pintype "passive"))
      (node (ref "C7") (pin "1") (pinfunction "1_1") (pintype "passive"))
      (node (ref "C8") (pin "1") (pinfunction "1_1") (pintype "passive"))
      (node (ref "C9") (pin "1") (pinfunction "1_1") (pintype "passive"))
      (node (ref "CH340") (pin "1") (pinfunction "GND_1") (pintype "passive"))
      (node (ref "CH340_2") (pin "1") (pinfunction "GND_1") (pintype "passive"))
      (node (ref "D1") (pin "K") (pinfunction "K_K") (pintype "passive"))
      (node (ref "D4") (pin "K") (pinfunction "K_K") (pintype "passive"))
      (node (ref "D6") (pin "A") (pinfunction "A_A") (pintype "passive"))
      (node (ref "D9") (pin "K") (pinfunction "K_K") (pintype "passive"))
      (node (ref "DC1") (pin "2") (pinfunction "2_2") (pintype "power_in"))
      (node (ref "DC1") (pin "3") (pinfunction "3_3") (pintype "power_in"))
      (node (ref "DHT11") (pin "4") (pinfunction "4_4") (pintype "passive"))
      (node (ref "IOPORTA") (pin "1") (pinfunction "1_1") (pintype "passive"))
      (node (ref "IOPORTA") (pin "23") (pinfunction "23_23") (pintype "passive"))
      (node (ref "IOPORTA") (pin "24") (pinfunction "24_24") (pintype "passive"))
      (node (ref "K1") (pin "1") (pinfunction "1_1") (pintype "passive"))
      (node (ref "LDO1") (pin "8") (pinfunction "8_8") (pintype "passive"))
      (node (ref "MAX3485") (pin "4") (pinfunction "DI_4") (pintype "passive"))
      (node (ref "MAX3485") (pin "5") (pinfunction "GND_5") (pintype "passive"))
      (node (ref "MPU9250") (pin "11") (pinfunction "11_11") (pintype "passive"))
      (node (ref "MPU9250") (pin "18") (pinfunction "18_18") (pintype "passive"))
      (node (ref "MPU9250") (pin "20") (pinfunction "20_20") (pintype "passive"))
      (node (ref "MPUBMP") (pin "5") (pinfunction "5_5") (pintype "passive"))
      (node (ref "PWM1") (pin "2") (pinfunction "2_2") (pintype "passive"))
      (node (ref "PWM2") (pin "2") (pinfunction "2_2") (pintype "passive"))
      (node (ref "PWM3") (pin "2") (pinfunction "2_2") (pintype "passive"))
      (node (ref "PWM4") (pin "2") (pinfunction "2_2") (pintype "passive"))
      (node (ref "Q1") (pin "2") (pinfunction "2_2") (pintype "passive"))
      (node (ref "R18") (pin "2") (pinfunction "2_2") (pintype "passive"))
      (node (ref "R3") (pin "2") (pinfunction "2_2") (pintype "passive"))
      (node (ref "R4") (pin "2") (pinfunction "2_2") (pintype "passive"))
      (node (ref "R6") (pin "2") (pinfunction "2_2") (pintype "passive"))
      (node (ref "R9") (pin "1") (pinfunction "1_1") (pintype "passive"))
      (node (ref "SWD") (pin "4") (pinfunction "4_4") (pintype "passive"))
      (node (ref "U1") (pin "10") (pinfunction "VSS_10") (pintype "power_in"))
      (node (ref "U1") (pin "20") (pinfunction "VSSA_20") (pintype "power_in"))
      (node (ref "U1") (pin "27") (pinfunction "VSS_27") (pintype "power_in"))
      (node (ref "U1") (pin "74") (pinfunction "VSS_74") (pintype "power_in"))
      (node (ref "U1") (pin "99") (pinfunction "VSS_99") (pintype "power_in"))
      (node (ref "USB1") (pin "5") (pinfunction "-_5") (pintype "passive"))
      (node (ref "USB2") (pin "5") (pinfunction "-_5") (pintype "passive"))
      (node (ref "USB2NUC") (pin "4") (pinfunction "4_4") (pintype "passive"))
      (node (ref "USB2NUC") (pin "5") (pinfunction "5_5") (pintype "passive"))
    )
    (net (code "103") (name "Net-(C21-Pad2)") (class "Default")
      (node (ref "C21") (pin "2") (pinfunction "2_2") (pintype "passive"))
      (node (ref "MPU9250") (pin "10") (pinfunction "10_10") (pintype "passive"))
    )
    (net (code "104") (name "Net-(CH340-XI)") (class "Default")
      (node (ref "C23") (pin "2") (pinfunction "2_2") (pintype "passive"))
      (node (ref "CH340") (pin "7") (pinfunction "XI_7") (pintype "passive"))
      (node (ref "X3") (pin "1") (pinfunction "1_1") (pintype "passive"))
    )
    (net (code "105") (name "Net-(CH340-XO)") (class "Default")
      (node (ref "C24") (pin "2") (pinfunction "2_2") (pintype "passive"))
      (node (ref "CH340") (pin "8") (pinfunction "XO_8") (pintype "passive"))
      (node (ref "X3") (pin "3") (pinfunction "3_3") (pintype "passive"))
    )
    (net (code "106") (name "Net-(CH340_2-XI)") (class "Default")
      (node (ref "C27") (pin "2") (pinfunction "2_2") (pintype "passive"))
      (node (ref "CH340_2") (pin "7") (pinfunction "XI_7") (pintype "passive"))
      (node (ref "X4") (pin "1") (pinfunction "1_1") (pintype "passive"))
    )
    (net (code "107") (name "Net-(CH340_2-XO)") (class "Default")
      (node (ref "C28") (pin "2") (pinfunction "2_2") (pintype "passive"))
      (node (ref "CH340_2") (pin "8") (pinfunction "XO_8") (pintype "passive"))
      (node (ref "X4") (pin "3") (pinfunction "3_3") (pintype "passive"))
    )
    (net (code "108") (name "Net-(D1-PadA)") (class "Default")
      (node (ref "D1") (pin "A") (pinfunction "A_A") (pintype "passive"))
      (node (ref "R7") (pin "1") (pinfunction "1_1") (pintype "passive"))
    )
    (net (code "109") (name "Net-(D2-PadA)") (class "Default")
      (node (ref "D2") (pin "A") (pinfunction "A_A") (pintype "passive"))
      (node (ref "R13") (pin "1") (pinfunction "1_1") (pintype "passive"))
    )
    (net (code "110") (name "Net-(D3-PadA)") (class "Default")
      (node (ref "D3") (pin "A") (pinfunction "A_A") (pintype "passive"))
      (node (ref "R14") (pin "1") (pinfunction "1_1") (pintype "passive"))
    )
    (net (code "111") (name "Net-(D7-PadA)") (class "Default")
      (node (ref "D7") (pin "A") (pinfunction "A_A") (pintype "passive"))
      (node (ref "R20") (pin "1") (pinfunction "1_1") (pintype "passive"))
    )
    (net (code "112") (name "Net-(D8-PadA)") (class "Default")
      (node (ref "D8") (pin "A") (pinfunction "A_A") (pintype "passive"))
      (node (ref "R21") (pin "1") (pinfunction "1_1") (pintype "passive"))
    )
    (net (code "113") (name "Net-(D9-PadA)") (class "Default")
      (node (ref "D9") (pin "A") (pinfunction "A_A") (pintype "passive"))
      (node (ref "R22") (pin "1") (pinfunction "1_1") (pintype "passive"))
    )
    (net (code "114") (name "Net-(DC1-Pad1)") (class "Default")
      (node (ref "DC1") (pin "1") (pinfunction "1_1") (pintype "power_in"))
      (node (ref "S1") (pin "2") (pinfunction "2_2") (pintype "passive"))
    )
    (net (code "115") (name "Net-(LDO1-Pad7)") (class "Default")
      (node (ref "LDO1") (pin "7") (pinfunction "7_7") (pintype "passive"))
      (node (ref "R5") (pin "2") (pinfunction "2_2") (pintype "passive"))
      (node (ref "R6") (pin "1") (pinfunction "1_1") (pintype "passive"))
    )
    (net (code "116") (name "Net-(MAX3485-A)") (class "Default")
      (node (ref "D5") (pin "A") (pinfunction "A_A") (pintype "passive"))
      (node (ref "D6") (pin "K") (pinfunction "K_K") (pintype "passive"))
      (node (ref "MAX3485") (pin "6") (pinfunction "A_6") (pintype "passive"))
      (node (ref "R19") (pin "2") (pinfunction "2_2") (pintype "passive"))
      (node (ref "RS485") (pin "1") (pinfunction "1_1") (pintype "passive"))
    )
    (net (code "117") (name "Net-(MAX3485-B)") (class "Default")
      (node (ref "D4") (pin "A") (pinfunction "A_A") (pintype "passive"))
      (node (ref "D5") (pin "K") (pinfunction "K_K") (pintype "passive"))
      (node (ref "MAX3485") (pin "7") (pinfunction "B_7") (pintype "passive"))
      (node (ref "R18") (pin "1") (pinfunction "1_1") (pintype "passive"))
      (node (ref "RS485") (pin "2") (pinfunction "2_2") (pintype "passive"))
    )
    (net (code "118") (name "Net-(MAX3485-DE)") (class "Default")
      (node (ref "MAX3485") (pin "2") (pinfunction "~{R}E_2") (pintype "passive"))
      (node (ref "MAX3485") (pin "3") (pinfunction "DE_3") (pintype "passive"))
      (node (ref "Q1") (pin "3") (pinfunction "3_3") (pintype "passive"))
      (node (ref "R16") (pin "1") (pinfunction "1_1") (pintype "passive"))
    )
    (net (code "119") (name "Net-(MAX3485-RO)") (class "Default")
      (node (ref "MAX3485") (pin "1") (pinfunction "RO_1") (pintype "passive"))
      (node (ref "R17") (pin "2") (pinfunction "2_2") (pintype "passive"))
    )
    (net (code "120") (name "Net-(Q1-Pad1)") (class "Default")
      (node (ref "Q1") (pin "1") (pinfunction "1_1") (pintype "passive"))
      (node (ref "R15") (pin "2") (pinfunction "2_2") (pintype "passive"))
    )
    (net (code "121") (name "Net-(U1A-VCAP_1)") (class "Default")
      (node (ref "C2") (pin "2") (pinfunction "2_2") (pintype "passive"))
      (node (ref "U1") (pin "49") (pinfunction "VCAP_1_49") (pintype "power_in"))
    )
    (net (code "122") (name "Net-(U1A-VCAP_2)") (class "Default")
      (node (ref "C1") (pin "2") (pinfunction "2_2") (pintype "passive"))
      (node (ref "U1") (pin "73") (pinfunction "VCAP_2_73") (pintype "power_in"))
    )
    (net (code "123") (name "V33") (class "Default")
      (node (ref "BMP280") (pin "6") (pinfunction "6_6") (pintype "passive"))
      (node (ref "BMP280") (pin "8") (pinfunction "8_8") (pintype "passive"))
      (node (ref "BOOT") (pin "2") (pinfunction "2_2") (pintype "passive"))
      (node (ref "BOOT") (pin "4") (pinfunction "4_4") (pintype "passive"))
      (node (ref "C10") (pin "2") (pinfunction "2_2") (pintype "passive"))
      (node (ref "C11") (pin "2") (pinfunction "2_2") (pintype "passive"))
      (node (ref "C12") (pin "2") (pinfunction "2_2") (pintype "passive"))
      (node (ref "C13") (pin "2") (pinfunction "2_2") (pintype "passive"))
      (node (ref "C14") (pin "2") (pinfunction "2_2") (pintype "passive"))
      (node (ref "C15") (pin "2") (pinfunction "2_2") (pintype "passive"))
      (node (ref "C18") (pin "2") (pinfunction "2_2") (pintype "passive"))
      (node (ref "C19") (pin "2") (pinfunction "2_2") (pintype "passive"))
      (node (ref "C20") (pin "2") (pinfunction "2_2") (pintype "passive"))
      (node (ref "C22") (pin "2") (pinfunction "2_2") (pintype "passive"))
      (node (ref "C25") (pin "2") (pinfunction "2_2") (pintype "passive"))
      (node (ref "C26") (pin "2") (pinfunction "2_2") (pintype "passive"))
      (node (ref "C29") (pin "2") (pinfunction "2_2") (pintype "passive"))
      (node (ref "C7") (pin "2") (pinfunction "2_2") (pintype "passive"))
      (node (ref "C8") (pin "2") (pinfunction "2_2") (pintype "passive"))
      (node (ref "C9") (pin "2") (pinfunction "2_2") (pintype "passive"))
      (node (ref "CH340") (pin "16") (pinfunction "VCC_16") (pintype "passive"))
      (node (ref "CH340") (pin "4") (pinfunction "V3.3_4") (pintype "passive"))
      (node (ref "CH340_2") (pin "16") (pinfunction "VCC_16") (pintype "passive"))
      (node (ref "CH340_2") (pin "4") (pinfunction "V3.3_4") (pintype "passive"))
      (node (ref "DHT11") (pin "1") (pinfunction "1_1") (pintype "passive"))
      (node (ref "LDO1") (pin "6") (pinfunction "6_6") (pintype "passive"))
      (node (ref "MAX3485") (pin "8") (pinfunction "VCC_8") (pintype "passive"))
      (node (ref "MPU9250") (pin "1") (pinfunction "1_1") (pintype "passive"))
      (node (ref "MPU9250") (pin "13") (pinfunction "13_13") (pintype "passive"))
      (node (ref "MPU9250") (pin "8") (pinfunction "8_8") (pintype "passive"))
      (node (ref "MPUBMP") (pin "1") (pinfunction "1_1") (pintype "passive"))
      (node (ref "MPUBMP") (pin "3") (pinfunction "3_3") (pintype "passive"))
      (node (ref "R10") (pin "2") (pinfunction "2_2") (pintype "passive"))
      (node (ref "R11") (pin "2") (pinfunction "2_2") (pintype "passive"))
      (node (ref "R12") (pin "2") (pinfunction "2_2") (pintype "passive"))
      (node (ref "R13") (pin "2") (pinfunction "2_2") (pintype "passive"))
      (node (ref "R14") (pin "2") (pinfunction "2_2") (pintype "passive"))
      (node (ref "R16") (pin "2") (pinfunction "2_2") (pintype "passive"))
      (node (ref "R19") (pin "1") (pinfunction "1_1") (pintype "passive"))
      (node (ref "R2") (pin "2") (pinfunction "2_2") (pintype "passive"))
      (node (ref "R20") (pin "2") (pinfunction "2_2") (pintype "passive"))
      (node (ref "R21") (pin "2") (pinfunction "2_2") (pintype "passive"))
      (node (ref "R5") (pin "1") (pinfunction "1_1") (pintype "passive"))
      (node (ref "R7") (pin "2") (pinfunction "2_2") (pintype "passive"))
      (node (ref "R8") (pin "2") (pinfunction "2_2") (pintype "passive"))
      (node (ref "U1") (pin "100") (pinfunction "VDD_100") (pintype "power_in"))
      (node (ref "U1") (pin "11") (pinfunction "VDD_11") (pintype "power_in"))
      (node (ref "U1") (pin "19") (pinfunction "VDD_19") (pintype "power_in"))
      (node (ref "U1") (pin "21") (pinfunction "VREF+_21") (pintype "power_in"))
      (node (ref "U1") (pin "22") (pinfunction "VDDA_22") (pintype "power_in"))
      (node (ref "U1") (pin "28") (pinfunction "VDD_28") (pintype "power_in"))
      (node (ref "U1") (pin "50") (pinfunction "VDD_50") (pintype "power_in"))
      (node (ref "U1") (pin "6") (pinfunction "VBAT_6") (pintype "power_in"))
      (node (ref "U1") (pin "75") (pinfunction "VDD_75") (pintype "power_in"))
    )
    (net (code "124") (name "VNUC5") (class "Default")
      (node (ref "IOPORTA") (pin "26") (pinfunction "26_26") (pintype "passive"))
      (node (ref "POWEREXT") (pin "2") (pinfunction "2_2") (pintype "passive"))
      (node (ref "R22") (pin "2") (pinfunction "2_2") (pintype "passive"))
      (node (ref "USB2NUC") (pin "1") (pinfunction "1_1") (pintype "passive"))
      (node (ref "USB2NUC") (pin "8") (pinfunction "8_8") (pintype "passive"))
    )
    (net (code "125") (name "VUSB_2") (class "Default")
      (node (ref "IOPORTB") (pin "20") (pinfunction "20_20") (pintype "passive"))
      (node (ref "USB1") (pin "1") (pinfunction "+_1") (pintype "passive"))
      (node (ref "USB2") (pin "1") (pinfunction "+_1") (pintype "passive"))
    )
    (net (code "126") (name "unconnected-(CH340-CTS#-Pad9)") (class "Default")
      (node (ref "CH340") (pin "9") (pinfunction "CTS#_9") (pintype "passive+no_connect"))
    )
    (net (code "127") (name "unconnected-(CH340-DCD#-Pad13)") (class "Default")
      (node (ref "CH340") (pin "13") (pinfunction "DCD#_13") (pintype "passive+no_connect"))
    )
    (net (code "128") (name "unconnected-(CH340-DSR#-Pad15)") (class "Default")
      (node (ref "CH340") (pin "15") (pinfunction "DSR#_15") (pintype "passive+no_connect"))
    )
    (net (code "129") (name "unconnected-(CH340-DTR#-Pad12)") (class "Default")
      (node (ref "CH340") (pin "12") (pinfunction "DTR#_12") (pintype "passive+no_connect"))
    )
    (net (code "130") (name "unconnected-(CH340-R232-Pad10)") (class "Default")
      (node (ref "CH340") (pin "10") (pinfunction "R232_10") (pintype "passive"))
    )
    (net (code "131") (name "unconnected-(CH340-RI#-Pad14)") (class "Default")
      (node (ref "CH340") (pin "14") (pinfunction "RI#_14") (pintype "passive+no_connect"))
    )
    (net (code "132") (name "unconnected-(CH340-RTS#-Pad11)") (class "Default")
      (node (ref "CH340") (pin "11") (pinfunction "RTS#_11") (pintype "passive+no_connect"))
    )
    (net (code "133") (name "unconnected-(CH340_2-CTS#-Pad9)") (class "Default")
      (node (ref "CH340_2") (pin "9") (pinfunction "CTS#_9") (pintype "passive+no_connect"))
    )
    (net (code "134") (name "unconnected-(CH340_2-DCD#-Pad13)") (class "Default")
      (node (ref "CH340_2") (pin "13") (pinfunction "DCD#_13") (pintype "passive+no_connect"))
    )
    (net (code "135") (name "unconnected-(CH340_2-DSR#-Pad15)") (class "Default")
      (node (ref "CH340_2") (pin "15") (pinfunction "DSR#_15") (pintype "passive+no_connect"))
    )
    (net (code "136") (name "unconnected-(CH340_2-DTR#-Pad12)") (class "Default")
      (node (ref "CH340_2") (pin "12") (pinfunction "DTR#_12") (pintype "passive+no_connect"))
    )
    (net (code "137") (name "unconnected-(CH340_2-R232-Pad10)") (class "Default")
      (node (ref "CH340_2") (pin "10") (pinfunction "R232_10") (pintype "passive"))
    )
    (net (code "138") (name "unconnected-(CH340_2-RI#-Pad14)") (class "Default")
      (node (ref "CH340_2") (pin "14") (pinfunction "RI#_14") (pintype "passive+no_connect"))
    )
    (net (code "139") (name "unconnected-(CH340_2-RTS#-Pad11)") (class "Default")
      (node (ref "CH340_2") (pin "11") (pinfunction "RTS#_11") (pintype "passive+no_connect"))
    )
    (net (code "140") (name "unconnected-(DHT11-Pad3)") (class "Default")
      (node (ref "DHT11") (pin "3") (pinfunction "3_3") (pintype "passive+no_connect"))
    )
    (net (code "141") (name "unconnected-(LDO1-Pad1)") (class "Default")
      (node (ref "LDO1") (pin "1") (pinfunction "1_1") (pintype "passive+no_connect"))
    )
    (net (code "142") (name "unconnected-(LDO1-Pad4)") (class "Default")
      (node (ref "LDO1") (pin "4") (pinfunction "4_4") (pintype "passive+no_connect"))
    )
    (net (code "143") (name "unconnected-(LDO1-Pad5)") (class "Default")
      (node (ref "LDO1") (pin "5") (pinfunction "5_5") (pintype "passive+no_connect"))
    )
    (net (code "144") (name "unconnected-(MPU9250-Pad2)") (class "Default")
      (node (ref "MPU9250") (pin "2") (pinfunction "2_2") (pintype "passive+no_connect"))
    )
    (net (code "145") (name "unconnected-(MPU9250-Pad3)") (class "Default")
      (node (ref "MPU9250") (pin "3") (pinfunction "3_3") (pintype "passive+no_connect"))
    )
    (net (code "146") (name "unconnected-(MPU9250-Pad4)") (class "Default")
      (node (ref "MPU9250") (pin "4") (pinfunction "4_4") (pintype "passive+no_connect"))
    )
    (net (code "147") (name "unconnected-(MPU9250-Pad5)") (class "Default")
      (node (ref "MPU9250") (pin "5") (pinfunction "5_5") (pintype "passive+no_connect"))
    )
    (net (code "148") (name "unconnected-(MPU9250-Pad6)") (class "Default")
      (node (ref "MPU9250") (pin "6") (pinfunction "6_6") (pintype "passive+no_connect"))
    )
    (net (code "149") (name "unconnected-(MPU9250-Pad7)") (class "Default")
      (node (ref "MPU9250") (pin "7") (pinfunction "7_7") (pintype "passive+no_connect"))
    )
    (net (code "150") (name "unconnected-(MPU9250-Pad14)") (class "Default")
      (node (ref "MPU9250") (pin "14") (pinfunction "14_14") (pintype "passive+no_connect"))
    )
    (net (code "151") (name "unconnected-(MPU9250-Pad15)") (class "Default")
      (node (ref "MPU9250") (pin "15") (pinfunction "15_15") (pintype "passive+no_connect"))
    )
    (net (code "152") (name "unconnected-(MPU9250-Pad16)") (class "Default")
      (node (ref "MPU9250") (pin "16") (pinfunction "16_16") (pintype "passive+no_connect"))
    )
    (net (code "153") (name "unconnected-(MPU9250-Pad17)") (class "Default")
      (node (ref "MPU9250") (pin "17") (pinfunction "17_17") (pintype "passive+no_connect"))
    )
    (net (code "154") (name "unconnected-(MPU9250-Pad19)") (class "Default")
      (node (ref "MPU9250") (pin "19") (pinfunction "19_19") (pintype "passive+no_connect"))
    )
    (net (code "155") (name "unconnected-(MPU9250-Pad21)") (class "Default")
      (node (ref "MPU9250") (pin "21") (pinfunction "21_21") (pintype "passive+no_connect"))
    )
    (net (code "156") (name "unconnected-(MPUBMP-Pad2)") (class "Default")
      (node (ref "MPUBMP") (pin "2") (pinfunction "2_2") (pintype "passive+no_connect"))
    )
    (net (code "157") (name "unconnected-(MPUBMP-Pad4)") (class "Default")
      (node (ref "MPUBMP") (pin "4") (pinfunction "4_4") (pintype "passive+no_connect"))
    )
    (net (code "158") (name "unconnected-(MPUBMP-Pad6)") (class "Default")
      (node (ref "MPUBMP") (pin "6") (pinfunction "6_6") (pintype "passive+no_connect"))
    )
    (net (code "159") (name "unconnected-(MPUBMP-Pad12)") (class "Default")
      (node (ref "MPUBMP") (pin "12") (pinfunction "12_12") (pintype "passive+no_connect"))
    )
    (net (code "160") (name "unconnected-(MPUBMP-Pad14)") (class "Default")
      (node (ref "MPUBMP") (pin "14") (pinfunction "14_14") (pintype "passive+no_connect"))
    )
    (net (code "161") (name "unconnected-(MPUBMP-Pad16)") (class "Default")
      (node (ref "MPUBMP") (pin "16") (pinfunction "16_16") (pintype "passive+no_connect"))
    )
    (net (code "162") (name "unconnected-(MPUBMP-Pad18)") (class "Default")
      (node (ref "MPUBMP") (pin "18") (pinfunction "18_18") (pintype "passive+no_connect"))
    )
    (net (code "163") (name "unconnected-(S1-Pad3)") (class "Default")
      (node (ref "S1") (pin "3") (pinfunction "3_3") (pintype "passive+no_connect"))
    )
    (net (code "164") (name "unconnected-(S1-Pad4)") (class "Default")
      (node (ref "S1") (pin "4") (pinfunction "4_4") (pintype "passive+no_connect"))
    )
    (net (code "165") (name "unconnected-(S1-Pad5)") (class "Default")
      (node (ref "S1") (pin "5") (pinfunction "5_5") (pintype "passive+no_connect"))
    )
    (net (code "166") (name "unconnected-(S1-Pad6)") (class "Default")
      (node (ref "S1") (pin "6") (pinfunction "6_6") (pintype "passive+no_connect"))
    )
    (net (code "167") (name "unconnected-(USB1-ID-Pad4)") (class "Default")
      (node (ref "USB1") (pin "4") (pinfunction "ID_4") (pintype "passive+no_connect"))
    )
    (net (code "168") (name "unconnected-(USB2-ID-Pad4)") (class "Default")
      (node (ref "USB2") (pin "4") (pinfunction "ID_4") (pintype "passive+no_connect"))
    )
    (net (code "169") (name "unconnected-(X2-Pad2)") (class "Default")
      (node (ref "X2") (pin "2") (pinfunction "2_2") (pintype "passive+no_connect"))
    )
    (net (code "170") (name "unconnected-(X2-Pad4)") (class "Default")
      (node (ref "X2") (pin "4") (pinfunction "4_4") (pintype "passive+no_connect"))
    )
    (net (code "171") (name "unconnected-(X3-Pad2)") (class "Default")
      (node (ref "X3") (pin "2") (pinfunction "2_2") (pintype "passive+no_connect"))
    )
    (net (code "172") (name "unconnected-(X3-Pad4)") (class "Default")
      (node (ref "X3") (pin "4") (pinfunction "4_4") (pintype "passive+no_connect"))
    )
    (net (code "173") (name "unconnected-(X4-Pad2)") (class "Default")
      (node (ref "X4") (pin "2") (pinfunction "2_2") (pintype "passive+no_connect"))
    )
    (net (code "174") (name "unconnected-(X4-Pad4)") (class "Default")
      (node (ref "X4") (pin "4") (pinfunction "4_4") (pintype "passive+no_connect"))
    )
  )
)
